# doppler_shield.net
KiCad netlist of a schematic drawn in EAGLE
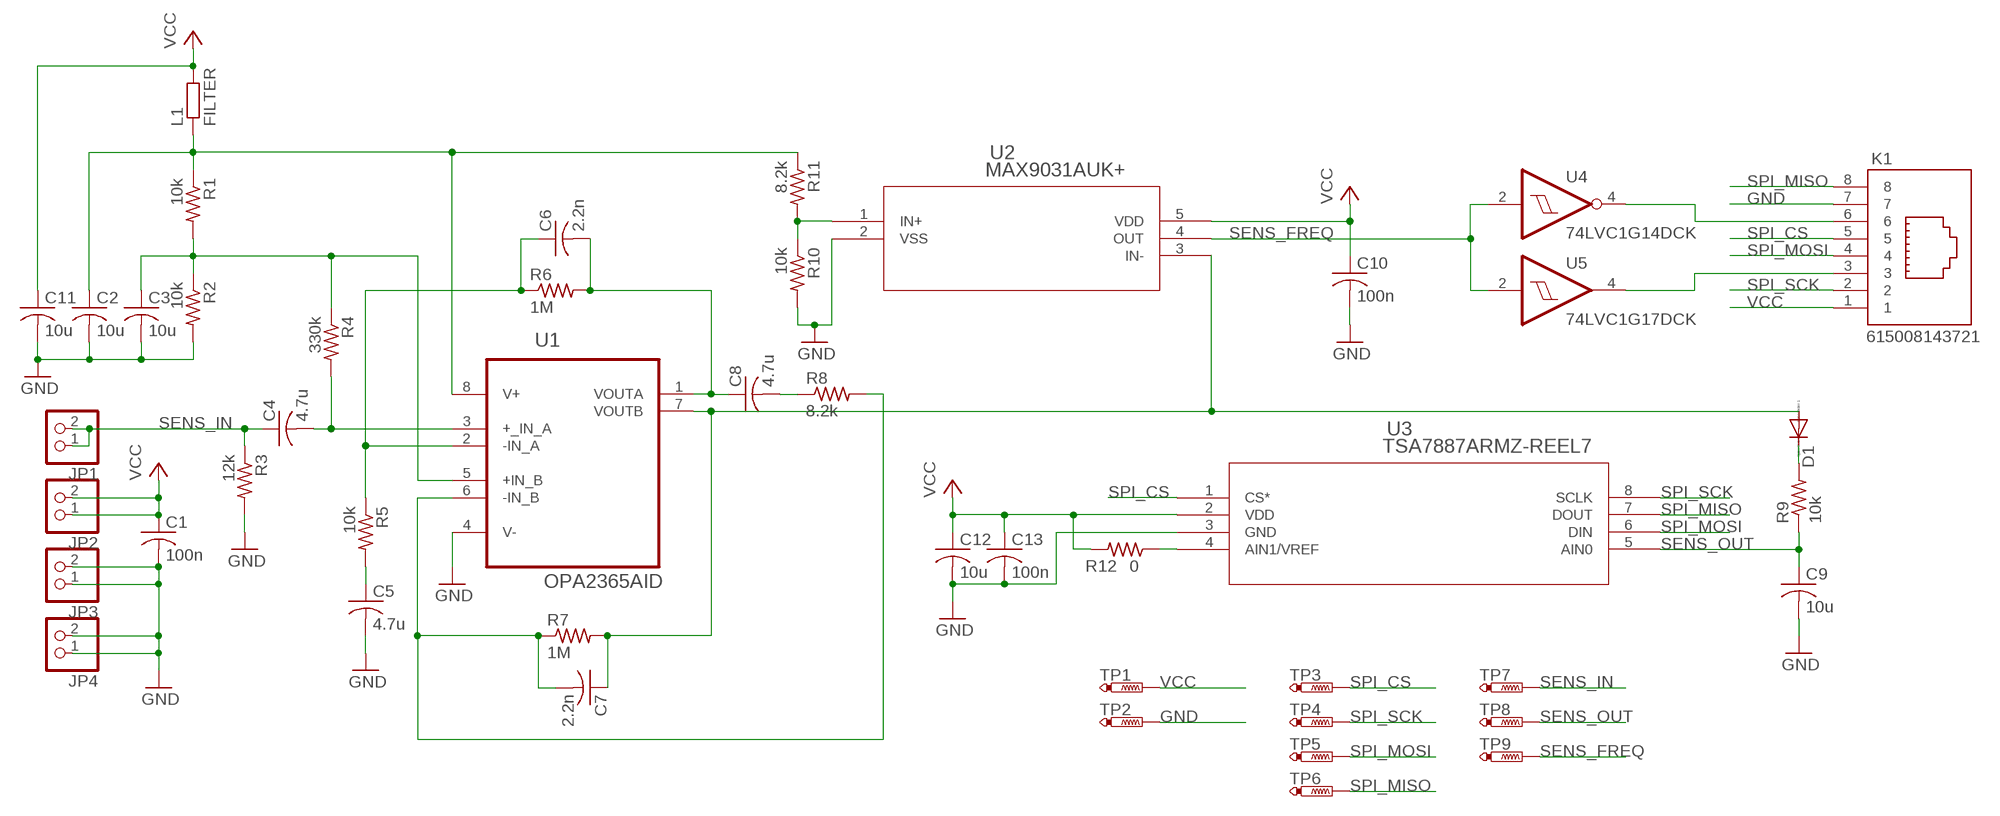
[diagram p0: schematic, sheet 1]

(export (version "E")
  (design (tool "Eeschema 10.0.6"))
  (components
    (comp (ref "C1")
      (value "100n")
      (footprint "eagle-import:C0805")
      (libsource (lib "eagle-import") (part "C-USC0805"))
    )
    (comp (ref "C2")
      (value "10u")
      (footprint "eagle-import:C0805")
      (libsource (lib "eagle-import") (part "C-USC0805"))
    )
    (comp (ref "C3")
      (value "10u")
      (footprint "eagle-import:C0805")
      (libsource (lib "eagle-import") (part "C-USC0805"))
    )
    (comp (ref "C4")
      (value "4.7u")
      (footprint "eagle-import:C0805")
      (libsource (lib "eagle-import") (part "C-USC0805"))
    )
    (comp (ref "C5")
      (value "4.7u")
      (footprint "eagle-import:C0805")
      (libsource (lib "eagle-import") (part "C-USC0805"))
    )
    (comp (ref "C6")
      (value "2.2n")
      (footprint "eagle-import:C0805")
      (libsource (lib "eagle-import") (part "C-USC0805"))
    )
    (comp (ref "C7")
      (value "2.2n")
      (footprint "eagle-import:C0805")
      (libsource (lib "eagle-import") (part "C-USC0805"))
    )
    (comp (ref "C8")
      (value "4.7u")
      (footprint "eagle-import:C0805")
      (libsource (lib "eagle-import") (part "C-USC0805"))
    )
    (comp (ref "C9")
      (value "10u")
      (footprint "eagle-import:C0805")
      (libsource (lib "eagle-import") (part "C-USC0805"))
    )
    (comp (ref "C10")
      (value "100n")
      (footprint "eagle-import:C0805")
      (libsource (lib "eagle-import") (part "C-USC0805"))
    )
    (comp (ref "C11")
      (value "10u")
      (footprint "eagle-import:C0805")
      (libsource (lib "eagle-import") (part "C-USC0805"))
    )
    (comp (ref "C12")
      (value "10u")
      (footprint "eagle-import:C0805")
      (libsource (lib "eagle-import") (part "C-USC0805"))
    )
    (comp (ref "C13")
      (value "100n")
      (footprint "eagle-import:C0805")
      (libsource (lib "eagle-import") (part "C-USC0805"))
    )
    (comp (ref "D1")
      (value "DIODE-DO214AC")
      (footprint "eagle-import:DO214AC")
      (libsource (lib "eagle-import") (part "DIODE-DO214AC"))
    )
    (comp (ref "JP1")
      (value "PINHD-1X2")
      (footprint "eagle-import:1X02")
      (libsource (lib "eagle-import") (part "PINHD-1X2"))
    )
    (comp (ref "JP2")
      (value "PINHD-1X2")
      (footprint "eagle-import:1X02")
      (libsource (lib "eagle-import") (part "PINHD-1X2"))
    )
    (comp (ref "JP3")
      (value "PINHD-1X2")
      (footprint "eagle-import:1X02")
      (libsource (lib "eagle-import") (part "PINHD-1X2"))
    )
    (comp (ref "JP4")
      (value "PINHD-1X2")
      (footprint "eagle-import:1X02")
      (libsource (lib "eagle-import") (part "PINHD-1X2"))
    )
    (comp (ref "K1")
      (value "615008143721")
      (footprint "eagle-import:615008143721")
      (libsource (lib "eagle-import") (part "615008143721"))
    )
    (comp (ref "L1")
      (value "FILTER")
      (footprint "eagle-import:R0805")
      (libsource (lib "eagle-import") (part "R-EU_R0805"))
    )
    (comp (ref "R1")
      (value "10k")
      (footprint "eagle-import:R0805")
      (libsource (lib "eagle-import") (part "R-US_R0805"))
    )
    (comp (ref "R2")
      (value "10k")
      (footprint "eagle-import:R0805")
      (libsource (lib "eagle-import") (part "R-US_R0805"))
    )
    (comp (ref "R3")
      (value "12k")
      (footprint "eagle-import:R0805")
      (libsource (lib "eagle-import") (part "R-US_R0805"))
    )
    (comp (ref "R4")
      (value "330k")
      (footprint "eagle-import:R0805")
      (libsource (lib "eagle-import") (part "R-US_R0805"))
    )
    (comp (ref "R5")
      (value "10k")
      (footprint "eagle-import:R0805")
      (libsource (lib "eagle-import") (part "R-US_R0805"))
    )
    (comp (ref "R6")
      (value "1M")
      (footprint "eagle-import:R0805")
      (libsource (lib "eagle-import") (part "R-US_R0805"))
    )
    (comp (ref "R7")
      (value "1M")
      (footprint "eagle-import:R0805")
      (libsource (lib "eagle-import") (part "R-US_R0805"))
    )
    (comp (ref "R8")
      (value "8.2k")
      (footprint "eagle-import:R0805")
      (libsource (lib "eagle-import") (part "R-US_R0805"))
    )
    (comp (ref "R9")
      (value "10k")
      (footprint "eagle-import:R0805")
      (libsource (lib "eagle-import") (part "R-US_R0805"))
    )
    (comp (ref "R10")
      (value "10k")
      (footprint "eagle-import:R0805")
      (libsource (lib "eagle-import") (part "R-US_R0805"))
    )
    (comp (ref "R11")
      (value "8.2k")
      (footprint "eagle-import:R0805")
      (libsource (lib "eagle-import") (part "R-US_R0805"))
    )
    (comp (ref "R12")
      (value "0")
      (footprint "eagle-import:R0805")
      (libsource (lib "eagle-import") (part "R-US_R0805"))
    )
    (comp (ref "TP1")
      (value "PTR1B1,27")
      (footprint "eagle-import:B1,27")
      (libsource (lib "eagle-import") (part "PTR1B1,27"))
    )
    (comp (ref "TP2")
      (value "PTR1B1,27")
      (footprint "eagle-import:B1,27")
      (libsource (lib "eagle-import") (part "PTR1B1,27"))
    )
    (comp (ref "TP3")
      (value "PTR1B1,27")
      (footprint "eagle-import:B1,27")
      (libsource (lib "eagle-import") (part "PTR1B1,27"))
    )
    (comp (ref "TP4")
      (value "PTR1B1,27")
      (footprint "eagle-import:B1,27")
      (libsource (lib "eagle-import") (part "PTR1B1,27"))
    )
    (comp (ref "TP5")
      (value "PTR1B1,27")
      (footprint "eagle-import:B1,27")
      (libsource (lib "eagle-import") (part "PTR1B1,27"))
    )
    (comp (ref "TP6")
      (value "PTR1B1,27")
      (footprint "eagle-import:B1,27")
      (libsource (lib "eagle-import") (part "PTR1B1,27"))
    )
    (comp (ref "TP7")
      (value "PTR1B1,27")
      (footprint "eagle-import:B1,27")
      (libsource (lib "eagle-import") (part "PTR1B1,27"))
    )
    (comp (ref "TP8")
      (value "PTR1B1,27")
      (footprint "eagle-import:B1,27")
      (libsource (lib "eagle-import") (part "PTR1B1,27"))
    )
    (comp (ref "TP9")
      (value "PTR1B1,27")
      (footprint "eagle-import:B1,27")
      (libsource (lib "eagle-import") (part "PTR1B1,27"))
    )
    (comp (ref "U1")
      (value "OPA2365AID")
      (footprint "eagle-import:SOIC127P600X175-8N")
      (libsource (lib "eagle-import") (part "OPA2365AID"))
    )
    (comp (ref "U2")
      (value "MAX9031AUK+")
      (footprint "eagle-import:21-0057F")
      (fields (field (name "MANUFACTURER_PART_NUMBER") "max9031auk+"))
      (libsource (lib "eagle-import") (part "MAX9031AUK+"))
    )
    (comp (ref "U3")
      (value "TSA7887ARMZ-REEL7")
      (footprint "eagle-import:RM_8")
      (fields
        (field (name "DIGIKEYPARTNUMBER") "AD7887ARMZ-REEL7-ND")
        (field (name "MANUFACTURER_PART_NUMBER") "AD7887ARMZ-REEL7")
        (field (name "COPYRIGHT") "Copyright (C) 2015 Accelerated Designs. All rights reserved")
      )
      (libsource (lib "eagle-import") (part "AD7887ARMZ-REEL7"))
    )
    (comp (ref "U4")
      (value "74LVC1G14DCK")
      (footprint "eagle-import:SC70-5")
      (libsource (lib "eagle-import") (part "741G14DCKLVC"))
    )
    (comp (ref "U5")
      (value "74LVC1G17DCK")
      (footprint "eagle-import:SC70-5")
      (libsource (lib "eagle-import") (part "741G17DCKLVC"))
    )
  )
  (nets
    (net (code "1") (name "/SENS_FREQ") (class "Default")
      (node (ref "TP9") (pin "TP") (pinfunction "TP_TP") (pintype "input"))
      (node (ref "U2") (pin "4") (pinfunction "OUT_4") (pintype "output"))
      (node (ref "U4") (pin "2") (pinfunction "I_2") (pintype "input"))
      (node (ref "U5") (pin "2") (pinfunction "I_2") (pintype "input"))
    )
    (net (code "2") (name "/SENS_IN") (class "Default")
      (node (ref "C4") (pin "1") (pinfunction "1_1") (pintype "passive"))
      (node (ref "JP1") (pin "1") (pinfunction "1_1") (pintype "passive"))
      (node (ref "JP1") (pin "2") (pinfunction "2_2") (pintype "passive"))
      (node (ref "R3") (pin "1") (pinfunction "1_1") (pintype "passive"))
      (node (ref "TP7") (pin "TP") (pinfunction "TP_TP") (pintype "input"))
    )
    (net (code "3") (name "/SENS_OUT") (class "Default")
      (node (ref "C9") (pin "1") (pinfunction "1_1") (pintype "passive"))
      (node (ref "R9") (pin "1") (pinfunction "1_1") (pintype "passive"))
      (node (ref "TP8") (pin "TP") (pinfunction "TP_TP") (pintype "input"))
      (node (ref "U3") (pin "5") (pinfunction "AIN0_5") (pintype "passive"))
    )
    (net (code "4") (name "/SPI_CS") (class "Default")
      (node (ref "K1") (pin "5") (pinfunction "5_5") (pintype "passive"))
      (node (ref "TP3") (pin "TP") (pinfunction "TP_TP") (pintype "input"))
      (node (ref "U3") (pin "1") (pinfunction "CS*_1") (pintype "passive"))
    )
    (net (code "5") (name "/SPI_MISO") (class "Default")
      (node (ref "K1") (pin "8") (pinfunction "8_8") (pintype "passive"))
      (node (ref "TP6") (pin "TP") (pinfunction "TP_TP") (pintype "input"))
      (node (ref "U3") (pin "7") (pinfunction "DOUT_7") (pintype "passive"))
    )
    (net (code "6") (name "/SPI_MOSI") (class "Default")
      (node (ref "K1") (pin "4") (pinfunction "4_4") (pintype "passive"))
      (node (ref "TP5") (pin "TP") (pinfunction "TP_TP") (pintype "input"))
      (node (ref "U3") (pin "6") (pinfunction "DIN_6") (pintype "passive"))
    )
    (net (code "7") (name "/SPI_SCK") (class "Default")
      (node (ref "K1") (pin "2") (pinfunction "2_2") (pintype "passive"))
      (node (ref "TP4") (pin "TP") (pinfunction "TP_TP") (pintype "input"))
      (node (ref "U3") (pin "8") (pinfunction "SCLK_8") (pintype "passive"))
    )
    (net (code "8") (name "GND") (class "Default")
      (node (ref "C1") (pin "2") (pinfunction "2_2") (pintype "passive"))
      (node (ref "C10") (pin "2") (pinfunction "2_2") (pintype "passive"))
      (node (ref "C11") (pin "2") (pinfunction "2_2") (pintype "passive"))
      (node (ref "C12") (pin "2") (pinfunction "2_2") (pintype "passive"))
      (node (ref "C13") (pin "2") (pinfunction "2_2") (pintype "passive"))
      (node (ref "C2") (pin "2") (pinfunction "2_2") (pintype "passive"))
      (node (ref "C3") (pin "2") (pinfunction "2_2") (pintype "passive"))
      (node (ref "C5") (pin "2") (pinfunction "2_2") (pintype "passive"))
      (node (ref "C9") (pin "2") (pinfunction "2_2") (pintype "passive"))
      (node (ref "JP3") (pin "1") (pinfunction "1_1") (pintype "passive"))
      (node (ref "JP3") (pin "2") (pinfunction "2_2") (pintype "passive"))
      (node (ref "JP4") (pin "1") (pinfunction "1_1") (pintype "passive"))
      (node (ref "JP4") (pin "2") (pinfunction "2_2") (pintype "passive"))
      (node (ref "K1") (pin "7") (pinfunction "7_7") (pintype "passive"))
      (node (ref "R10") (pin "2") (pinfunction "2_2") (pintype "passive"))
      (node (ref "R2") (pin "2") (pinfunction "2_2") (pintype "passive"))
      (node (ref "R3") (pin "2") (pinfunction "2_2") (pintype "passive"))
      (node (ref "TP2") (pin "TP") (pinfunction "TP_TP") (pintype "input"))
      (node (ref "U1") (pin "4") (pinfunction "V-_4") (pintype "power_in"))
      (node (ref "U2") (pin "2") (pinfunction "VSS_2") (pintype "power_in"))
      (node (ref "U3") (pin "3") (pinfunction "GND_3") (pintype "passive"))
    )
    (net (code "9") (name "Net-(C5-Pad1)") (class "Default")
      (node (ref "C5") (pin "1") (pinfunction "1_1") (pintype "passive"))
      (node (ref "R5") (pin "2") (pinfunction "2_2") (pintype "passive"))
    )
    (net (code "10") (name "Net-(C8-Pad2)") (class "Default")
      (node (ref "C8") (pin "2") (pinfunction "2_2") (pintype "passive"))
      (node (ref "R8") (pin "1") (pinfunction "1_1") (pintype "passive"))
    )
    (net (code "11") (name "Net-(D1-PadC)") (class "Default")
      (node (ref "D1") (pin "C") (pinfunction "C_C") (pintype "passive"))
      (node (ref "R9") (pin "2") (pinfunction "2_2") (pintype "passive"))
    )
    (net (code "12") (name "Net-(U1-+IN_B)") (class "Default")
      (node (ref "C3") (pin "1") (pinfunction "1_1") (pintype "passive"))
      (node (ref "R1") (pin "2") (pinfunction "2_2") (pintype "passive"))
      (node (ref "R2") (pin "1") (pinfunction "1_1") (pintype "passive"))
      (node (ref "R4") (pin "1") (pinfunction "1_1") (pintype "passive"))
      (node (ref "U1") (pin "5") (pinfunction "+IN_B_5") (pintype "input"))
    )
    (net (code "13") (name "Net-(U1-+_IN_A)") (class "Default")
      (node (ref "C4") (pin "2") (pinfunction "2_2") (pintype "passive"))
      (node (ref "R4") (pin "2") (pinfunction "2_2") (pintype "passive"))
      (node (ref "U1") (pin "3") (pinfunction "+_IN_A_3") (pintype "input"))
    )
    (net (code "14") (name "Net-(U1--IN_A)") (class "Default")
      (node (ref "C6") (pin "1") (pinfunction "1_1") (pintype "passive"))
      (node (ref "R5") (pin "1") (pinfunction "1_1") (pintype "passive"))
      (node (ref "R6") (pin "1") (pinfunction "1_1") (pintype "passive"))
      (node (ref "U1") (pin "2") (pinfunction "-IN_A_2") (pintype "input"))
    )
    (net (code "15") (name "Net-(U1--IN_B)") (class "Default")
      (node (ref "C7") (pin "2") (pinfunction "2_2") (pintype "passive"))
      (node (ref "R7") (pin "1") (pinfunction "1_1") (pintype "passive"))
      (node (ref "R8") (pin "2") (pinfunction "2_2") (pintype "passive"))
      (node (ref "U1") (pin "6") (pinfunction "-IN_B_6") (pintype "input"))
    )
    (net (code "16") (name "Net-(U1-V+)") (class "Default")
      (node (ref "C2") (pin "1") (pinfunction "1_1") (pintype "passive"))
      (node (ref "L1") (pin "1") (pinfunction "1_1") (pintype "passive"))
      (node (ref "R1") (pin "1") (pinfunction "1_1") (pintype "passive"))
      (node (ref "R11") (pin "1") (pinfunction "1_1") (pintype "passive"))
      (node (ref "U1") (pin "8") (pinfunction "V+_8") (pintype "power_in"))
    )
    (net (code "17") (name "Net-(U1-VOUTA)") (class "Default")
      (node (ref "C6") (pin "2") (pinfunction "2_2") (pintype "passive"))
      (node (ref "C8") (pin "1") (pinfunction "1_1") (pintype "passive"))
      (node (ref "R6") (pin "2") (pinfunction "2_2") (pintype "passive"))
      (node (ref "U1") (pin "1") (pinfunction "VOUTA_1") (pintype "output"))
    )
    (net (code "18") (name "Net-(U1-VOUTB)") (class "Default")
      (node (ref "C7") (pin "1") (pinfunction "1_1") (pintype "passive"))
      (node (ref "D1") (pin "A") (pinfunction "A_A") (pintype "passive"))
      (node (ref "R7") (pin "2") (pinfunction "2_2") (pintype "passive"))
      (node (ref "U1") (pin "7") (pinfunction "VOUTB_7") (pintype "output"))
      (node (ref "U2") (pin "3") (pinfunction "IN-_3") (pintype "input"))
    )
    (net (code "19") (name "Net-(U2-IN+)") (class "Default")
      (node (ref "R10") (pin "1") (pinfunction "1_1") (pintype "passive"))
      (node (ref "R11") (pin "2") (pinfunction "2_2") (pintype "passive"))
      (node (ref "U2") (pin "1") (pinfunction "IN+_1") (pintype "input"))
    )
    (net (code "20") (name "Net-(U3-AIN1{slash}VREF)") (class "Default")
      (node (ref "R12") (pin "1") (pinfunction "1_1") (pintype "passive"))
      (node (ref "U3") (pin "4") (pinfunction "AIN1/VREF_4") (pintype "passive"))
    )
    (net (code "21") (name "Net-(U4A-O)") (class "Default")
      (node (ref "K1") (pin "6") (pinfunction "6_6") (pintype "passive"))
      (node (ref "U4") (pin "4") (pinfunction "O_4") (pintype "output"))
    )
    (net (code "22") (name "Net-(U5A-O)") (class "Default")
      (node (ref "K1") (pin "3") (pinfunction "3_3") (pintype "passive"))
      (node (ref "U5") (pin "4") (pinfunction "O_4") (pintype "output"))
    )
    (net (code "23") (name "VCC") (class "Default")
      (node (ref "C1") (pin "1") (pinfunction "1_1") (pintype "passive"))
      (node (ref "C10") (pin "1") (pinfunction "1_1") (pintype "passive"))
      (node (ref "C11") (pin "1") (pinfunction "1_1") (pintype "passive"))
      (node (ref "C12") (pin "1") (pinfunction "1_1") (pintype "passive"))
      (node (ref "C13") (pin "1") (pinfunction "1_1") (pintype "passive"))
      (node (ref "JP2") (pin "1") (pinfunction "1_1") (pintype "passive"))
      (node (ref "JP2") (pin "2") (pinfunction "2_2") (pintype "passive"))
      (node (ref "K1") (pin "1") (pinfunction "1_1") (pintype "passive"))
      (node (ref "L1") (pin "2") (pinfunction "2_2") (pintype "passive"))
      (node (ref "R12") (pin "2") (pinfunction "2_2") (pintype "passive"))
      (node (ref "TP1") (pin "TP") (pinfunction "TP_TP") (pintype "input"))
      (node (ref "U2") (pin "5") (pinfunction "VDD_5") (pintype "power_in"))
      (node (ref "U3") (pin "2") (pinfunction "VDD_2") (pintype "power_in"))
    )
  )
)
